# Sheet1.net
KiCad netlist of a schematic drawn in Altium Designer
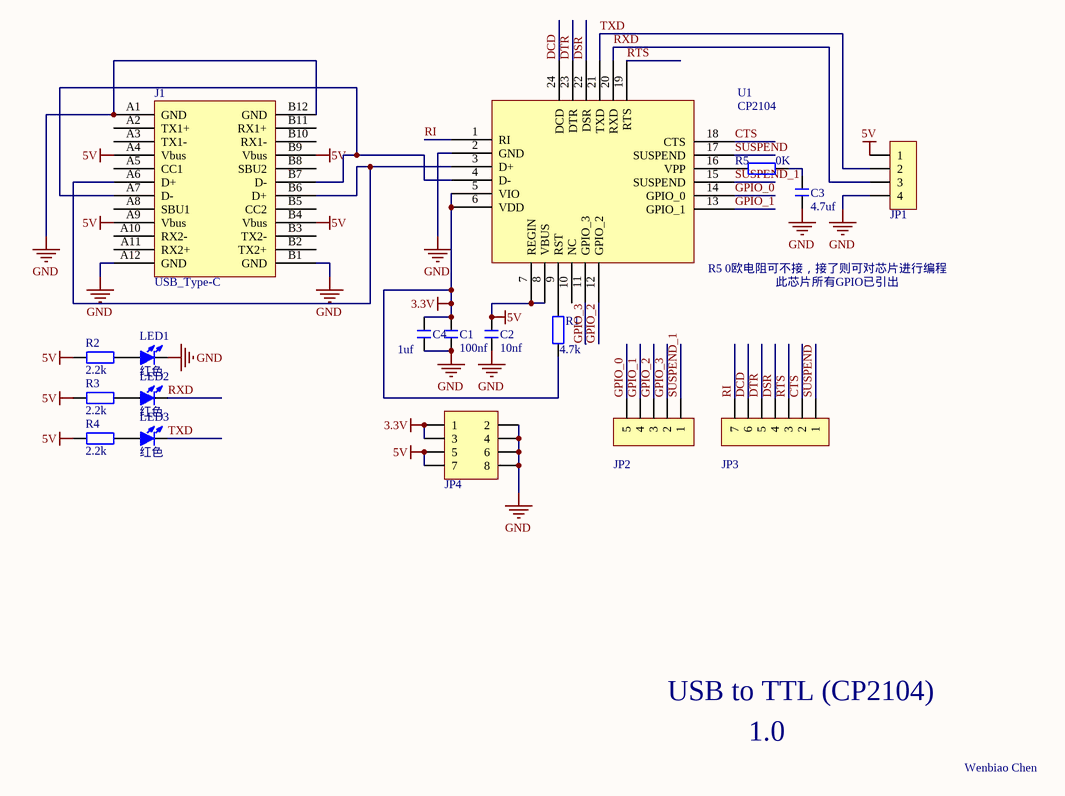
[diagram p0: Sheet1.SchDoc]

(export (version "E")
  (design (tool "Eeschema 10.0.6"))
  (components
    (comp (ref "C1")
      (value "100nf")
      (footprint "C 0402_L")
      (description "贴片电容")
      (libsource (lib "0.1 - 电阻-电容-电感") (part "C"))
    )
    (comp (ref "C2")
      (value "10nf")
      (footprint "C 0402_L")
      (description "贴片电容")
      (libsource (lib "0.1 - 电阻-电容-电感") (part "C"))
    )
    (comp (ref "C3")
      (value "4.7uf")
      (footprint "C 0402_L")
      (description "贴片电容")
      (libsource (lib "0.1 - 电阻-电容-电感") (part "C"))
    )
    (comp (ref "C4")
      (value "1uf")
      (footprint "C 0402_L")
      (description "贴片电容")
      (libsource (lib "0.1 - 电阻-电容-电感") (part "C"))
    )
    (comp (ref "J1")
      (value "USB_Type-C")
      (footprint "Type_C-UJ31-CH-G2-SMT-TR(Primary)")
      (libsource (lib "USB") (part "USB_Type-C"))
    )
    (comp (ref "JP1")
      (value "HDR-1X4")
      (footprint "HDR2.54-LI-4P")
      (description "4P接插件")
      (fields (field (name "版权归属") "封装库来自淘宝 ID：黄晶宝石"))
      (libsource (lib "5.4 - 接插件-脚距2.54 (100mil) ") (part "Header 4"))
    )
    (comp (ref "JP2")
      (value "HDR-1X5")
      (footprint "HDR2.54-LI-5P")
      (description "5P接插件")
      (fields (field (name "版权归属") "封装库来自淘宝 ID：黄晶宝石"))
      (libsource (lib "5.4 - 接插件-脚距2.54 (100mil) ") (part "Header 5"))
    )
    (comp (ref "JP3")
      (value "HDR-1X7")
      (footprint "HDR2.54-LI-7P")
      (description "7P接插件")
      (fields (field (name "版权归属") "封装库来自淘宝 ID：黄晶宝石"))
      (libsource (lib "5.4 - 接插件-脚距2.54 (100mil) ") (part "Header 7"))
    )
    (comp (ref "JP4")
      (value "Header 4X2")
      (footprint "HDR2.54-LI-2x4P")
      (description "4*2P接插件")
      (fields (field (name "版权归属") "封装库来自淘宝 ID：黄晶宝石"))
      (libsource (lib "5.4 - 接插件-脚距2.54 (100mil) ") (part "Header 4X2"))
    )
    (comp (ref "LED1")
      (value "红色")
      (footprint "LED 0603B")
      (description "贴片LED")
      (fields (field (name "版权归属") "封装库来自淘宝 ID：黄晶宝石"))
      (libsource (lib "0.3 - LED发光二极管") (part "LED-SMD"))
    )
    (comp (ref "LED2")
      (value "红色")
      (footprint "LED 0603Y")
      (description "贴片LED")
      (fields (field (name "版权归属") "封装库来自淘宝 ID：黄晶宝石"))
      (libsource (lib "0.3 - LED发光二极管") (part "LED-SMD"))
    )
    (comp (ref "LED3")
      (value "红色")
      (footprint "LED 0603G")
      (description "贴片LED")
      (fields (field (name "版权归属") "封装库来自淘宝 ID：黄晶宝石"))
      (libsource (lib "0.3 - LED发光二极管") (part "LED-SMD"))
    )
    (comp (ref "R1")
      (value "4.7k")
      (footprint "R 0402_L")
      (description "贴片电阻")
      (fields (field (name "版权归属") "来自淘宝 ID：黄晶宝石"))
      (libsource (lib "0.1 - 电阻-电容-电感") (part "R"))
    )
    (comp (ref "R2")
      (value "2.2k")
      (footprint "R 0402_L")
      (description "贴片电阻")
      (fields (field (name "版权归属") "来自淘宝 ID：黄晶宝石"))
      (libsource (lib "0.1 - 电阻-电容-电感") (part "R"))
    )
    (comp (ref "R3")
      (value "2.2k")
      (footprint "R 0402_L")
      (description "贴片电阻")
      (fields (field (name "版权归属") "来自淘宝 ID：黄晶宝石"))
      (libsource (lib "0.1 - 电阻-电容-电感") (part "R"))
    )
    (comp (ref "R4")
      (value "2.2k")
      (footprint "R 0402_L")
      (description "贴片电阻")
      (fields (field (name "版权归属") "来自淘宝 ID：黄晶宝石"))
      (libsource (lib "0.1 - 电阻-电容-电感") (part "R"))
    )
    (comp (ref "R5")
      (value "0K")
      (footprint "R 0402_L")
      (description "贴片电阻")
      (fields (field (name "版权归属") "来自淘宝 ID：黄晶宝石"))
      (libsource (lib "0.1 - 电阻-电容-电感") (part "R"))
    )
    (comp (ref "U1") (value "CP2104") (footprint "CP2104") (libsource (lib "USB") (part "CP2104")))
  )
  (nets
    (net (code "1") (name "/CTS") (class "Default")
      (node (ref "JP3") (pin "2") (pinfunction "2_2") (pintype "passive"))
      (node (ref "U1") (pin "18") (pinfunction "CTS_18") (pintype "passive"))
    )
    (net (code "2") (name "/DCD") (class "Default")
      (node (ref "JP3") (pin "6") (pinfunction "6_6") (pintype "passive"))
      (node (ref "U1") (pin "24") (pinfunction "DCD_24") (pintype "passive"))
    )
    (net (code "3") (name "/DSR") (class "Default")
      (node (ref "JP3") (pin "4") (pinfunction "4_4") (pintype "passive"))
      (node (ref "U1") (pin "22") (pinfunction "DSR_22") (pintype "passive"))
    )
    (net (code "4") (name "/DTR") (class "Default")
      (node (ref "JP3") (pin "5") (pinfunction "5_5") (pintype "passive"))
      (node (ref "U1") (pin "23") (pinfunction "DTR_23") (pintype "passive"))
    )
    (net (code "5") (name "/GPIO_0") (class "Default")
      (node (ref "JP2") (pin "5") (pinfunction "5_5") (pintype "passive"))
      (node (ref "U1") (pin "14") (pinfunction "GPIO_0_14") (pintype "passive"))
    )
    (net (code "6") (name "/GPIO_1") (class "Default")
      (node (ref "JP2") (pin "4") (pinfunction "4_4") (pintype "passive"))
      (node (ref "U1") (pin "13") (pinfunction "GPIO_1_13") (pintype "passive"))
    )
    (net (code "7") (name "/GPIO_2") (class "Default")
      (node (ref "JP2") (pin "3") (pinfunction "3_3") (pintype "passive"))
      (node (ref "U1") (pin "12") (pinfunction "GPIO_2_12") (pintype "passive"))
    )
    (net (code "8") (name "/GPIO_3") (class "Default")
      (node (ref "JP2") (pin "2") (pinfunction "2_2") (pintype "passive"))
      (node (ref "U1") (pin "11") (pinfunction "GPIO_3_11") (pintype "passive"))
    )
    (net (code "9") (name "/RI") (class "Default")
      (node (ref "JP3") (pin "7") (pinfunction "7_7") (pintype "passive"))
      (node (ref "U1") (pin "1") (pinfunction "RI_1") (pintype "passive"))
    )
    (net (code "10") (name "/RTS") (class "Default")
      (node (ref "JP3") (pin "3") (pinfunction "3_3") (pintype "passive"))
      (node (ref "U1") (pin "19") (pinfunction "RTS_19") (pintype "passive"))
    )
    (net (code "11") (name "/RXD") (class "Default")
      (node (ref "JP1") (pin "3") (pinfunction "3_3") (pintype "passive"))
      (node (ref "LED2") (pin "2") (pinfunction "K_2") (pintype "passive"))
      (node (ref "U1") (pin "20") (pinfunction "RXD_20") (pintype "passive"))
    )
    (net (code "12") (name "/SUSPEND") (class "Default")
      (node (ref "JP3") (pin "1") (pinfunction "1_1") (pintype "passive"))
      (node (ref "U1") (pin "17") (pinfunction "SUSPEND_17") (pintype "passive"))
    )
    (net (code "13") (name "/SUSPEND_1") (class "Default")
      (node (ref "JP2") (pin "1") (pinfunction "1_1") (pintype "passive"))
      (node (ref "U1") (pin "15") (pinfunction "SUSPEND_15") (pintype "passive"))
    )
    (net (code "14") (name "/TXD") (class "Default")
      (node (ref "JP1") (pin "2") (pinfunction "2_2") (pintype "passive"))
      (node (ref "LED3") (pin "2") (pinfunction "K_2") (pintype "passive"))
      (node (ref "U1") (pin "21") (pinfunction "TXD_21") (pintype "passive"))
    )
    (net (code "15") (name "3.3V") (class "Default")
      (node (ref "C1") (pin "1") (pinfunction "1_1") (pintype "passive"))
      (node (ref "C4") (pin "1") (pinfunction "1_1") (pintype "passive"))
      (node (ref "JP4") (pin "1") (pinfunction "1_1") (pintype "passive"))
      (node (ref "JP4") (pin "3") (pinfunction "3_3") (pintype "passive"))
      (node (ref "R1") (pin "2") (pinfunction "2_2") (pintype "passive"))
      (node (ref "U1") (pin "5") (pinfunction "VIO_5") (pintype "passive"))
      (node (ref "U1") (pin "6") (pinfunction "VDD_6") (pintype "passive"))
    )
    (net (code "16") (name "5V") (class "Default")
      (node (ref "C2") (pin "1") (pinfunction "1_1") (pintype "passive"))
      (node (ref "J1") (pin "A4") (pinfunction "Vbus_A4") (pintype "passive"))
      (node (ref "J1") (pin "A9") (pinfunction "Vbus_A9") (pintype "passive"))
      (node (ref "J1") (pin "B4") (pinfunction "Vbus_B4") (pintype "passive"))
      (node (ref "J1") (pin "B9") (pinfunction "Vbus_B9") (pintype "passive"))
      (node (ref "JP1") (pin "1") (pinfunction "1_1") (pintype "passive"))
      (node (ref "JP4") (pin "5") (pinfunction "5_5") (pintype "passive"))
      (node (ref "JP4") (pin "7") (pinfunction "7_7") (pintype "passive"))
      (node (ref "R2") (pin "1") (pinfunction "1_1") (pintype "passive"))
      (node (ref "R3") (pin "1") (pinfunction "1_1") (pintype "passive"))
      (node (ref "R4") (pin "1") (pinfunction "1_1") (pintype "passive"))
      (node (ref "U1") (pin "7") (pinfunction "REGIN_7") (pintype "passive"))
      (node (ref "U1") (pin "8") (pinfunction "VBUS_8") (pintype "passive"))
    )
    (net (code "17") (name "GND") (class "Default")
      (node (ref "C1") (pin "2") (pinfunction "2_2") (pintype "passive"))
      (node (ref "C2") (pin "2") (pinfunction "2_2") (pintype "passive"))
      (node (ref "C3") (pin "1") (pinfunction "1_1") (pintype "passive"))
      (node (ref "C4") (pin "2") (pinfunction "2_2") (pintype "passive"))
      (node (ref "J1") (pin "A1") (pinfunction "GND_A1") (pintype "passive"))
      (node (ref "J1") (pin "A12") (pinfunction "GND_A12") (pintype "passive"))
      (node (ref "J1") (pin "B1") (pinfunction "GND_B1") (pintype "passive"))
      (node (ref "J1") (pin "B12") (pinfunction "GND_B12") (pintype "passive"))
      (node (ref "JP1") (pin "4") (pinfunction "4_4") (pintype "passive"))
      (node (ref "JP4") (pin "2") (pinfunction "2_2") (pintype "passive"))
      (node (ref "JP4") (pin "4") (pinfunction "4_4") (pintype "passive"))
      (node (ref "JP4") (pin "6") (pinfunction "6_6") (pintype "passive"))
      (node (ref "JP4") (pin "8") (pinfunction "8_8") (pintype "passive"))
      (node (ref "LED1") (pin "2") (pinfunction "K_2") (pintype "passive"))
      (node (ref "U1") (pin "2") (pinfunction "GND_2") (pintype "passive"))
    )
    (net (code "18") (name "Net-(C3-Pad2)") (class "Default")
      (node (ref "C3") (pin "2") (pinfunction "2_2") (pintype "passive"))
      (node (ref "R5") (pin "2") (pinfunction "2_2") (pintype "passive"))
    )
    (net (code "19") (name "Net-(LED1-A)") (class "Default")
      (node (ref "LED1") (pin "1") (pinfunction "A_1") (pintype "passive"))
      (node (ref "R2") (pin "2") (pinfunction "2_2") (pintype "passive"))
    )
    (net (code "20") (name "Net-(LED2-A)") (class "Default")
      (node (ref "LED2") (pin "1") (pinfunction "A_1") (pintype "passive"))
      (node (ref "R3") (pin "2") (pinfunction "2_2") (pintype "passive"))
    )
    (net (code "21") (name "Net-(LED3-A)") (class "Default")
      (node (ref "LED3") (pin "1") (pinfunction "A_1") (pintype "passive"))
      (node (ref "R4") (pin "2") (pinfunction "2_2") (pintype "passive"))
    )
    (net (code "22") (name "Net-(U1-D+)") (class "Default")
      (node (ref "J1") (pin "A6") (pinfunction "D+_A6") (pintype "passive"))
      (node (ref "J1") (pin "B6") (pinfunction "D+_B6") (pintype "passive"))
      (node (ref "U1") (pin "3") (pinfunction "D+_3") (pintype "passive"))
    )
    (net (code "23") (name "Net-(U1-D-)") (class "Default")
      (node (ref "J1") (pin "A7") (pinfunction "D-_A7") (pintype "passive"))
      (node (ref "J1") (pin "B7") (pinfunction "D-_B7") (pintype "passive"))
      (node (ref "U1") (pin "4") (pinfunction "D-_4") (pintype "passive"))
    )
    (net (code "24") (name "Net-(U1-RST)") (class "Default")
      (node (ref "R1") (pin "1") (pinfunction "1_1") (pintype "passive"))
      (node (ref "U1") (pin "9") (pinfunction "RST_9") (pintype "passive"))
    )
    (net (code "25") (name "Net-(U1-VPP)") (class "Default")
      (node (ref "R5") (pin "1") (pinfunction "1_1") (pintype "passive"))
      (node (ref "U1") (pin "16") (pinfunction "VPP_16") (pintype "passive"))
    )
    (net (code "26") (name "unconnected-(J1-CC1-PadA5)") (class "Default")
      (node (ref "J1") (pin "A5") (pinfunction "CC1_A5") (pintype "passive"))
    )
    (net (code "27") (name "unconnected-(J1-CC2-PadB5)") (class "Default")
      (node (ref "J1") (pin "B5") (pinfunction "CC2_B5") (pintype "passive"))
    )
    (net (code "28") (name "unconnected-(J1-RX1+-PadB11)") (class "Default")
      (node (ref "J1") (pin "B11") (pinfunction "RX1+_B11") (pintype "passive"))
    )
    (net (code "29") (name "unconnected-(J1-RX1--PadB10)") (class "Default")
      (node (ref "J1") (pin "B10") (pinfunction "RX1-_B10") (pintype "passive"))
    )
    (net (code "30") (name "unconnected-(J1-RX2+-PadA11)") (class "Default")
      (node (ref "J1") (pin "A11") (pinfunction "RX2+_A11") (pintype "passive"))
    )
    (net (code "31") (name "unconnected-(J1-RX2--PadA10)") (class "Default")
      (node (ref "J1") (pin "A10") (pinfunction "RX2-_A10") (pintype "passive"))
    )
    (net (code "32") (name "unconnected-(J1-SBU1-PadA8)") (class "Default")
      (node (ref "J1") (pin "A8") (pinfunction "SBU1_A8") (pintype "passive"))
    )
    (net (code "33") (name "unconnected-(J1-SBU2-PadB8)") (class "Default")
      (node (ref "J1") (pin "B8") (pinfunction "SBU2_B8") (pintype "passive"))
    )
    (net (code "34") (name "unconnected-(J1-TX1+-PadA2)") (class "Default")
      (node (ref "J1") (pin "A2") (pinfunction "TX1+_A2") (pintype "passive"))
    )
    (net (code "35") (name "unconnected-(J1-TX1--PadA3)") (class "Default")
      (node (ref "J1") (pin "A3") (pinfunction "TX1-_A3") (pintype "passive"))
    )
    (net (code "36") (name "unconnected-(J1-TX2+-PadB2)") (class "Default")
      (node (ref "J1") (pin "B2") (pinfunction "TX2+_B2") (pintype "passive"))
    )
    (net (code "37") (name "unconnected-(J1-TX2--PadB3)") (class "Default")
      (node (ref "J1") (pin "B3") (pinfunction "TX2-_B3") (pintype "passive"))
    )
    (net (code "38") (name "unconnected-(U1-NC-Pad10)") (class "Default")
      (node (ref "U1") (pin "10") (pinfunction "NC_10") (pintype "passive"))
    )
  )
)
